# EtchSketch.net
KiCad netlist of a schematic drawn in EAGLE
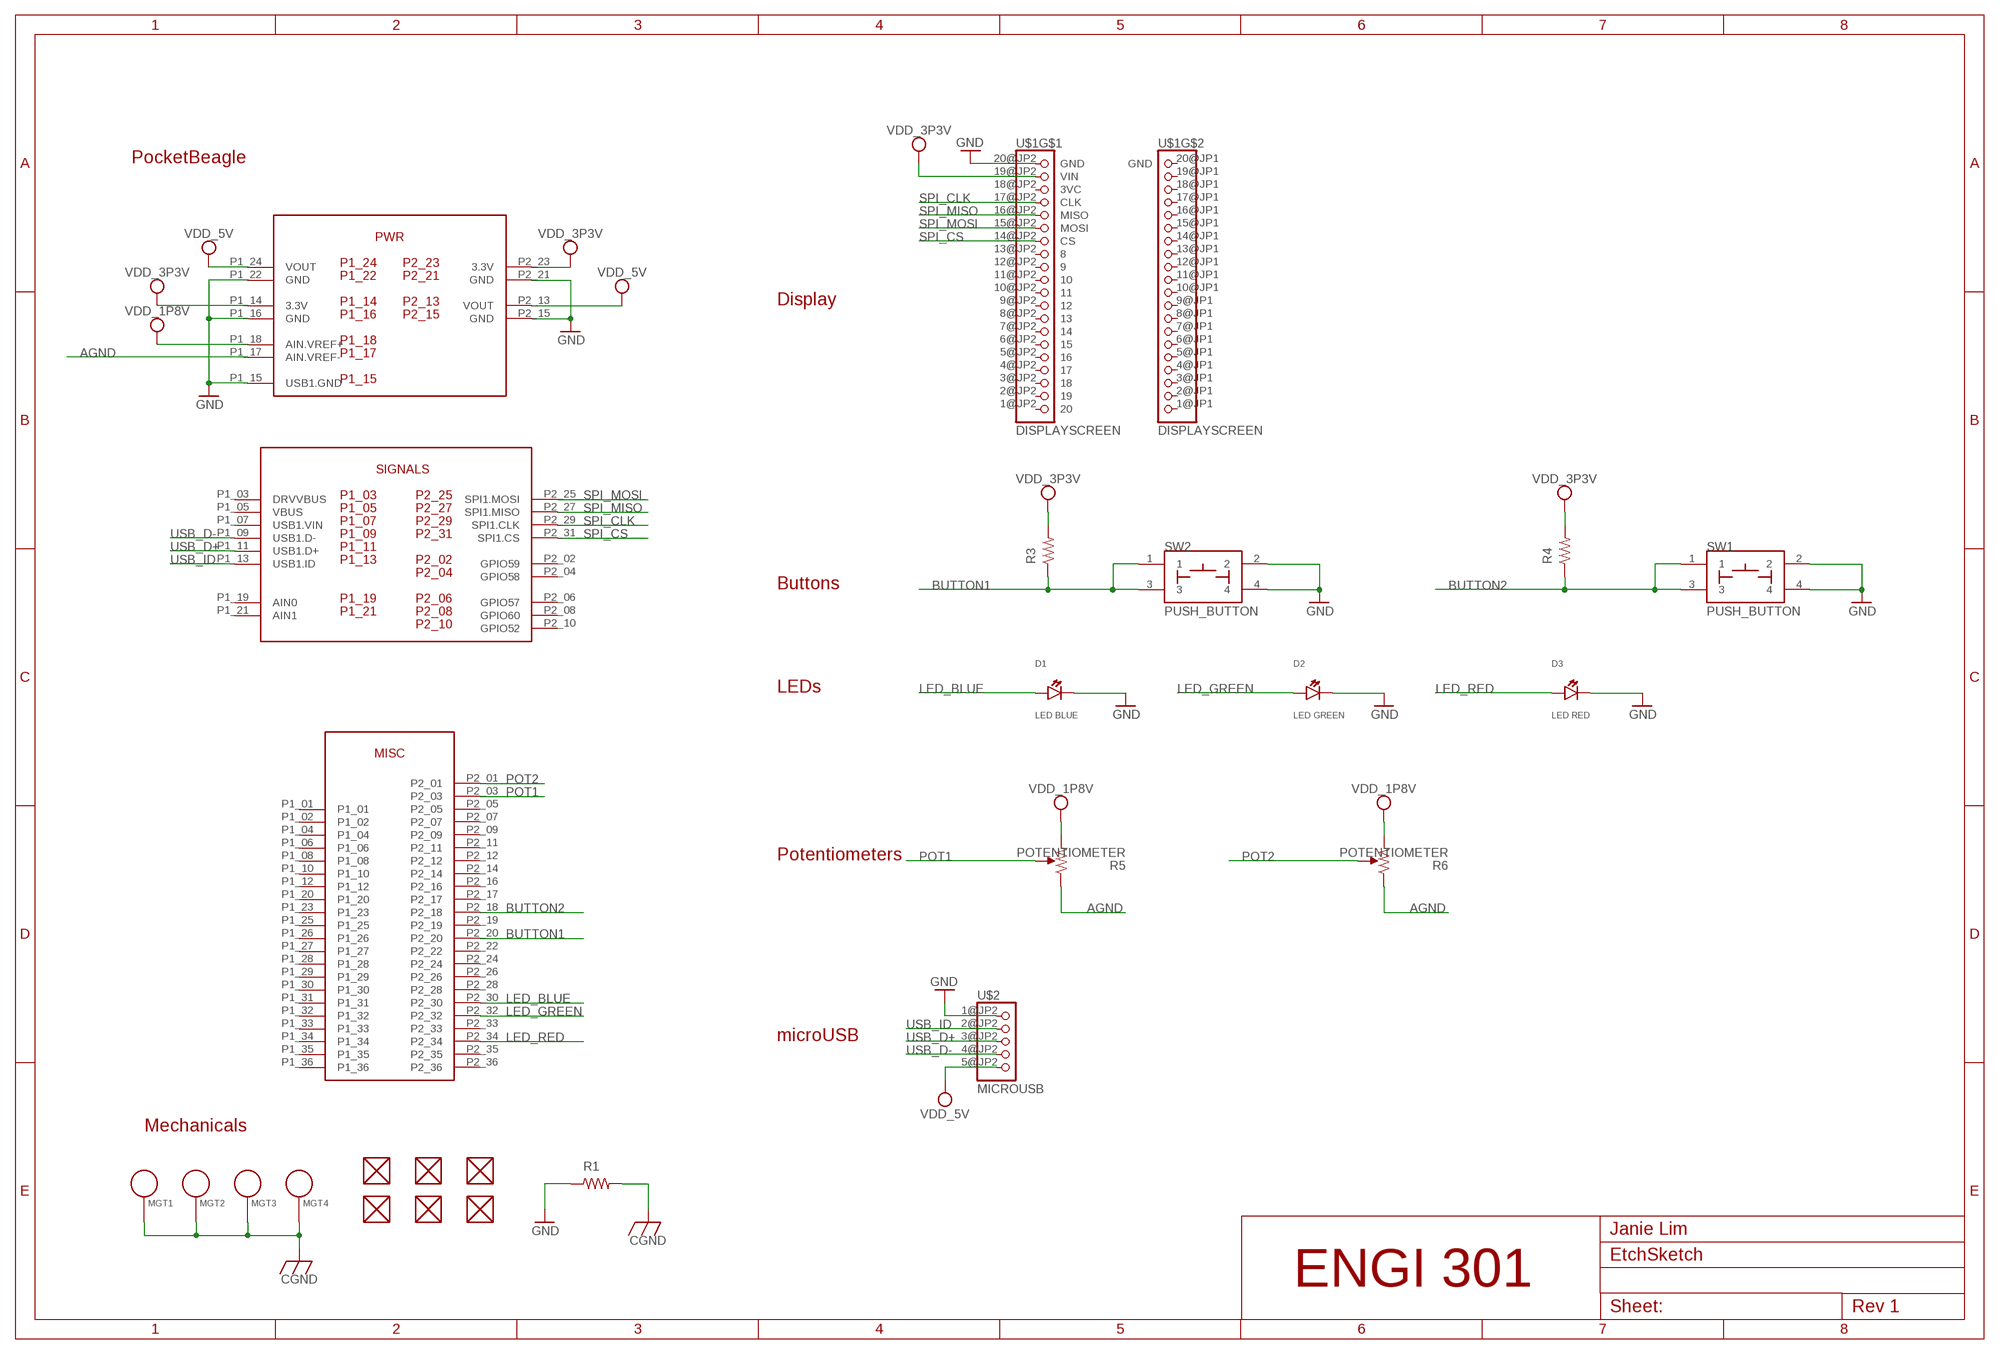
[diagram p0: schematic, sheet 1]

(export (version "E")
  (design (tool "Eeschema 10.0.6"))
  (components
    (comp (ref "D1")
      (value "LED BLUE")
      (footprint "eagle-import:EIA-STD")
      (libsource (lib "eagle-import") (part "LED"))
    )
    (comp (ref "D2")
      (value "LED GREEN")
      (footprint "eagle-import:EIA-STD")
      (libsource (lib "eagle-import") (part "LED"))
    )
    (comp (ref "D3")
      (value "LED RED")
      (footprint "eagle-import:EIA-STD")
      (libsource (lib "eagle-import") (part "LED"))
    )
    (comp (ref "FUD1")
      (value "FIDUCIAL")
      (footprint "eagle-import:FIDUCIAL_40MIL")
      (libsource (lib "eagle-import") (part "FIDUCIAL"))
    )
    (comp (ref "FUD2")
      (value "FIDUCIAL")
      (footprint "eagle-import:FIDUCIAL_40MIL")
      (libsource (lib "eagle-import") (part "FIDUCIAL"))
    )
    (comp (ref "FUD3")
      (value "FIDUCIAL")
      (footprint "eagle-import:FIDUCIAL_40MIL")
      (libsource (lib "eagle-import") (part "FIDUCIAL"))
    )
    (comp (ref "FUD4")
      (value "FIDUCIAL")
      (footprint "eagle-import:FIDUCIAL_40MIL")
      (libsource (lib "eagle-import") (part "FIDUCIAL"))
    )
    (comp (ref "FUD5")
      (value "FIDUCIAL")
      (footprint "eagle-import:FIDUCIAL_40MIL")
      (libsource (lib "eagle-import") (part "FIDUCIAL"))
    )
    (comp (ref "FUD6")
      (value "FIDUCIAL")
      (footprint "eagle-import:FIDUCIAL_40MIL")
      (libsource (lib "eagle-import") (part "FIDUCIAL"))
    )
    (comp (ref "MGT1")
      (value "MOUNTING_HOLE")
      (footprint "eagle-import:MOUNTING_HOLE")
      (libsource (lib "eagle-import") (part "MOUNTING_HOLE"))
    )
    (comp (ref "MGT2")
      (value "MOUNTING_HOLE")
      (footprint "eagle-import:MOUNTING_HOLE")
      (libsource (lib "eagle-import") (part "MOUNTING_HOLE"))
    )
    (comp (ref "MGT3")
      (value "MOUNTING_HOLE")
      (footprint "eagle-import:MOUNTING_HOLE")
      (libsource (lib "eagle-import") (part "MOUNTING_HOLE"))
    )
    (comp (ref "MGT4")
      (value "MOUNTING_HOLE")
      (footprint "eagle-import:MOUNTING_HOLE")
      (libsource (lib "eagle-import") (part "MOUNTING_HOLE"))
    )
    (comp (ref "R1")
      (value "R_R0603")
      (footprint "eagle-import:R0603")
      (libsource (lib "eagle-import") (part "R_R0603"))
    )
    (comp (ref "R3")
      (value "R_R0603")
      (footprint "eagle-import:R0603")
      (libsource (lib "eagle-import") (part "R_R0603"))
    )
    (comp (ref "R4")
      (value "R_R0603")
      (footprint "eagle-import:R0603")
      (libsource (lib "eagle-import") (part "R_R0603"))
    )
    (comp (ref "R5")
      (value "POTENTIOMETER")
      (footprint "eagle-import:POT-PO90S")
      (libsource (lib "eagle-import") (part "POTENTIOMETER"))
    )
    (comp (ref "R6")
      (value "POTENTIOMETER")
      (footprint "eagle-import:POT-PO90S")
      (libsource (lib "eagle-import") (part "POTENTIOMETER"))
    )
    (comp (ref "SW1")
      (value "PUSH_BUTTON")
      (footprint "eagle-import:BUTTON_12.5MM")
      (libsource (lib "eagle-import") (part "PUSH_BUTTON"))
    )
    (comp (ref "SW2")
      (value "PUSH_BUTTON")
      (footprint "eagle-import:BUTTON_12.5MM")
      (libsource (lib "eagle-import") (part "PUSH_BUTTON"))
    )
    (comp (ref "U$1")
      (value "DISPLAYSCREEN")
      (footprint "eagle-import:DISPLAYSCREEN")
      (libsource (lib "eagle-import") (part "DISPLAYSCREEN"))
    )
    (comp (ref "U$2")
      (value "MICROUSB")
      (footprint "eagle-import:MICROUSB")
      (libsource (lib "eagle-import") (part "MICROUSB"))
    )
    (comp (ref "U1")
      (value "POCKETBEAGLE_NEW")
      (footprint "eagle-import:POCKETBEAGLE")
      (libsource (lib "eagle-import") (part "POCKETBEAGLE_NEW"))
    )
  )
  (nets
    (net (code "1") (name "/AGND") (class "Default")
      (node (ref "R5") (pin "CCW") (pinfunction "CCW_CCW") (pintype "passive"))
      (node (ref "R6") (pin "CCW") (pinfunction "CCW_CCW") (pintype "passive"))
      (node (ref "U1") (pin "P1_17") (pinfunction "AIN.VREF-_P1_17") (pintype "bidirectional"))
    )
    (net (code "2") (name "/BUTTON1") (class "Default")
      (node (ref "R3") (pin "1") (pinfunction "1_1") (pintype "passive"))
      (node (ref "SW2") (pin "1") (pinfunction "1_1") (pintype "bidirectional"))
      (node (ref "SW2") (pin "3") (pinfunction "3_3") (pintype "bidirectional"))
      (node (ref "U1") (pin "P2_20") (pinfunction "P2_20_P2_20") (pintype "bidirectional"))
    )
    (net (code "3") (name "/BUTTON2") (class "Default")
      (node (ref "R4") (pin "1") (pinfunction "1_1") (pintype "passive"))
      (node (ref "SW1") (pin "1") (pinfunction "1_1") (pintype "bidirectional"))
      (node (ref "SW1") (pin "3") (pinfunction "3_3") (pintype "bidirectional"))
      (node (ref "U1") (pin "P2_18") (pinfunction "P2_18_P2_18") (pintype "bidirectional"))
    )
    (net (code "4") (name "/LED_BLUE") (class "Default")
      (node (ref "D1") (pin "ANODE") (pinfunction "ANODE_ANODE") (pintype "bidirectional"))
      (node (ref "U1") (pin "P2_30") (pinfunction "P2_30_P2_30") (pintype "bidirectional"))
    )
    (net (code "5") (name "/LED_GREEN") (class "Default")
      (node (ref "D2") (pin "ANODE") (pinfunction "ANODE_ANODE") (pintype "bidirectional"))
      (node (ref "U1") (pin "P2_32") (pinfunction "P2_32_P2_32") (pintype "bidirectional"))
    )
    (net (code "6") (name "/LED_RED") (class "Default")
      (node (ref "D3") (pin "ANODE") (pinfunction "ANODE_ANODE") (pintype "bidirectional"))
      (node (ref "U1") (pin "P2_34") (pinfunction "P2_34_P2_34") (pintype "bidirectional"))
    )
    (net (code "7") (name "/POT1") (class "Default")
      (node (ref "R5") (pin "S") (pinfunction "S_S") (pintype "bidirectional"))
      (node (ref "U1") (pin "P2_03") (pinfunction "P2_03_P2_03") (pintype "bidirectional"))
    )
    (net (code "8") (name "/POT2") (class "Default")
      (node (ref "R6") (pin "S") (pinfunction "S_S") (pintype "bidirectional"))
      (node (ref "U1") (pin "P2_01") (pinfunction "P2_01_P2_01") (pintype "bidirectional"))
    )
    (net (code "9") (name "/SPI_CLK") (class "Default")
      (node (ref "U$1") (pin "17@JP2") (pinfunction "CLK_17@JP2") (pintype "passive"))
      (node (ref "U1") (pin "P2_29") (pinfunction "SPI1.CLK_P2_29") (pintype "bidirectional"))
    )
    (net (code "10") (name "/SPI_CS") (class "Default")
      (node (ref "U$1") (pin "14@JP2") (pinfunction "CS_14@JP2") (pintype "passive"))
      (node (ref "U1") (pin "P2_31") (pinfunction "SPI1.CS_P2_31") (pintype "bidirectional"))
    )
    (net (code "11") (name "/SPI_MISO") (class "Default")
      (node (ref "U$1") (pin "16@JP2") (pinfunction "MISO_16@JP2") (pintype "passive"))
      (node (ref "U1") (pin "P2_27") (pinfunction "SPI1.MISO_P2_27") (pintype "bidirectional"))
    )
    (net (code "12") (name "/SPI_MOSI") (class "Default")
      (node (ref "U$1") (pin "15@JP2") (pinfunction "MOSI_15@JP2") (pintype "passive"))
      (node (ref "U1") (pin "P2_25") (pinfunction "SPI1.MOSI_P2_25") (pintype "bidirectional"))
    )
    (net (code "13") (name "/USB_D+") (class "Default")
      (node (ref "U$2") (pin "3@JP2") (pinfunction "D+_3@JP2") (pintype "passive"))
      (node (ref "U1") (pin "P1_11") (pinfunction "USB1.D+_P1_11") (pintype "bidirectional"))
    )
    (net (code "14") (name "/USB_D-") (class "Default")
      (node (ref "U$2") (pin "4@JP2") (pinfunction "D-_4@JP2") (pintype "passive"))
      (node (ref "U1") (pin "P1_09") (pinfunction "USB1.D-_P1_09") (pintype "bidirectional"))
    )
    (net (code "15") (name "/USB_ID") (class "Default")
      (node (ref "U$2") (pin "2@JP2") (pinfunction "ID_2@JP2") (pintype "passive"))
      (node (ref "U1") (pin "P1_13") (pinfunction "USB1.ID_P1_13") (pintype "bidirectional"))
    )
    (net (code "16") (name "CGND") (class "Default")
      (node (ref "MGT1") (pin "P$1") (pinfunction "P$1_P$1") (pintype "bidirectional"))
      (node (ref "MGT2") (pin "P$1") (pinfunction "P$1_P$1") (pintype "bidirectional"))
      (node (ref "MGT3") (pin "P$1") (pinfunction "P$1_P$1") (pintype "bidirectional"))
      (node (ref "MGT4") (pin "P$1") (pinfunction "P$1_P$1") (pintype "bidirectional"))
      (node (ref "R1") (pin "2") (pinfunction "2_2") (pintype "passive"))
    )
    (net (code "17") (name "GND") (class "Default")
      (node (ref "D1") (pin "CATHODE") (pinfunction "CATHODE_CATHODE") (pintype "bidirectional"))
      (node (ref "D2") (pin "CATHODE") (pinfunction "CATHODE_CATHODE") (pintype "bidirectional"))
      (node (ref "D3") (pin "CATHODE") (pinfunction "CATHODE_CATHODE") (pintype "bidirectional"))
      (node (ref "R1") (pin "1") (pinfunction "1_1") (pintype "passive"))
      (node (ref "SW1") (pin "2") (pinfunction "2_2") (pintype "bidirectional"))
      (node (ref "SW1") (pin "4") (pinfunction "4_4") (pintype "bidirectional"))
      (node (ref "SW2") (pin "2") (pinfunction "2_2") (pintype "bidirectional"))
      (node (ref "SW2") (pin "4") (pinfunction "4_4") (pintype "bidirectional"))
      (node (ref "U$1") (pin "20@JP2") (pinfunction "GND_20@JP2") (pintype "passive"))
      (node (ref "U$2") (pin "1@JP2") (pinfunction "GND_1@JP2") (pintype "passive"))
      (node (ref "U1") (pin "P1_15") (pinfunction "USB1.GND_P1_15") (pintype "bidirectional"))
      (node (ref "U1") (pin "P1_16") (pinfunction "GND_P1_16") (pintype "power_in"))
      (node (ref "U1") (pin "P1_22") (pinfunction "GND_P1_22") (pintype "power_in"))
      (node (ref "U1") (pin "P2_15") (pinfunction "GND_P2_15") (pintype "power_in"))
      (node (ref "U1") (pin "P2_21") (pinfunction "GND_P2_21") (pintype "power_in"))
    )
    (net (code "18") (name "VDD_1P8V") (class "Default")
      (node (ref "R5") (pin "CW") (pinfunction "CW_CW") (pintype "passive"))
      (node (ref "R6") (pin "CW") (pinfunction "CW_CW") (pintype "passive"))
      (node (ref "U1") (pin "P1_18") (pinfunction "AIN.VREF+_P1_18") (pintype "bidirectional"))
    )
    (net (code "19") (name "VDD_3P3V") (class "Default")
      (node (ref "R3") (pin "2") (pinfunction "2_2") (pintype "passive"))
      (node (ref "R4") (pin "2") (pinfunction "2_2") (pintype "passive"))
      (node (ref "U$1") (pin "19@JP2") (pinfunction "VIN_19@JP2") (pintype "passive"))
      (node (ref "U1") (pin "P1_14") (pinfunction "3.3V_P1_14") (pintype "power_in"))
      (node (ref "U1") (pin "P2_23") (pinfunction "3.3V_P2_23") (pintype "power_in"))
    )
    (net (code "20") (name "VDD_5V") (class "Default")
      (node (ref "U$2") (pin "5@JP2") (pinfunction "5V_5@JP2") (pintype "passive"))
      (node (ref "U1") (pin "P1_24") (pinfunction "VOUT_P1_24") (pintype "power_in"))
      (node (ref "U1") (pin "P2_13") (pinfunction "VOUT_P2_13") (pintype "power_in"))
    )
    (net (code "21") (name "unconnected-(FUD1-PadP$1)") (class "Default")
      (node (ref "FUD1") (pin "P$1") (pinfunction "P$1_P$1") (pintype "no_connect"))
    )
    (net (code "22") (name "unconnected-(FUD2-PadP$1)") (class "Default")
      (node (ref "FUD2") (pin "P$1") (pinfunction "P$1_P$1") (pintype "no_connect"))
    )
    (net (code "23") (name "unconnected-(FUD3-PadP$1)") (class "Default")
      (node (ref "FUD3") (pin "P$1") (pinfunction "P$1_P$1") (pintype "no_connect"))
    )
    (net (code "24") (name "unconnected-(FUD4-PadP$1)") (class "Default")
      (node (ref "FUD4") (pin "P$1") (pinfunction "P$1_P$1") (pintype "no_connect"))
    )
    (net (code "25") (name "unconnected-(FUD5-PadP$1)") (class "Default")
      (node (ref "FUD5") (pin "P$1") (pinfunction "P$1_P$1") (pintype "no_connect"))
    )
    (net (code "26") (name "unconnected-(FUD6-PadP$1)") (class "Default")
      (node (ref "FUD6") (pin "P$1") (pinfunction "P$1_P$1") (pintype "no_connect"))
    )
    (net (code "27") (name "unconnected-(U$1A-3VC-Pad18@JP2)") (class "Default")
      (node (ref "U$1") (pin "18@JP2") (pinfunction "3VC_18@JP2") (pintype "passive"))
    )
    (net (code "28") (name "unconnected-(U$1A-8-Pad13@JP2)") (class "Default")
      (node (ref "U$1") (pin "13@JP2") (pinfunction "8_13@JP2") (pintype "passive"))
    )
    (net (code "29") (name "unconnected-(U$1A-9-Pad12@JP2)") (class "Default")
      (node (ref "U$1") (pin "12@JP2") (pinfunction "9_12@JP2") (pintype "passive"))
    )
    (net (code "30") (name "unconnected-(U$1A-10-Pad11@JP2)") (class "Default")
      (node (ref "U$1") (pin "11@JP2") (pinfunction "10_11@JP2") (pintype "passive"))
    )
    (net (code "31") (name "unconnected-(U$1A-11-Pad10@JP2)") (class "Default")
      (node (ref "U$1") (pin "10@JP2") (pinfunction "11_10@JP2") (pintype "passive"))
    )
    (net (code "32") (name "unconnected-(U$1A-12-Pad9@JP2)") (class "Default")
      (node (ref "U$1") (pin "9@JP2") (pinfunction "12_9@JP2") (pintype "passive"))
    )
    (net (code "33") (name "unconnected-(U$1A-13-Pad8@JP2)") (class "Default")
      (node (ref "U$1") (pin "8@JP2") (pinfunction "13_8@JP2") (pintype "passive"))
    )
    (net (code "34") (name "unconnected-(U$1A-14-Pad7@JP2)") (class "Default")
      (node (ref "U$1") (pin "7@JP2") (pinfunction "14_7@JP2") (pintype "passive"))
    )
    (net (code "35") (name "unconnected-(U$1A-15-Pad6@JP2)") (class "Default")
      (node (ref "U$1") (pin "6@JP2") (pinfunction "15_6@JP2") (pintype "passive"))
    )
    (net (code "36") (name "unconnected-(U$1A-16-Pad5@JP2)") (class "Default")
      (node (ref "U$1") (pin "5@JP2") (pinfunction "16_5@JP2") (pintype "passive"))
    )
    (net (code "37") (name "unconnected-(U$1A-17-Pad4@JP2)") (class "Default")
      (node (ref "U$1") (pin "4@JP2") (pinfunction "17_4@JP2") (pintype "passive"))
    )
    (net (code "38") (name "unconnected-(U$1A-18-Pad3@JP2)") (class "Default")
      (node (ref "U$1") (pin "3@JP2") (pinfunction "18_3@JP2") (pintype "passive"))
    )
    (net (code "39") (name "unconnected-(U$1A-19-Pad2@JP2)") (class "Default")
      (node (ref "U$1") (pin "2@JP2") (pinfunction "19_2@JP2") (pintype "passive"))
    )
    (net (code "40") (name "unconnected-(U$1A-20-Pad1@JP2)") (class "Default")
      (node (ref "U$1") (pin "1@JP2") (pinfunction "20_1@JP2") (pintype "passive"))
    )
    (net (code "41") (name "unconnected-(U$1B-2-Pad19@JP1)") (class "Default")
      (node (ref "U$1") (pin "19@JP1") (pinfunction "2_19@JP1") (pintype "passive"))
    )
    (net (code "42") (name "unconnected-(U$1B-3-Pad18@JP1)") (class "Default")
      (node (ref "U$1") (pin "18@JP1") (pinfunction "3_18@JP1") (pintype "passive"))
    )
    (net (code "43") (name "unconnected-(U$1B-4-Pad17@JP1)") (class "Default")
      (node (ref "U$1") (pin "17@JP1") (pinfunction "4_17@JP1") (pintype "passive"))
    )
    (net (code "44") (name "unconnected-(U$1B-5-Pad16@JP1)") (class "Default")
      (node (ref "U$1") (pin "16@JP1") (pinfunction "5_16@JP1") (pintype "passive"))
    )
    (net (code "45") (name "unconnected-(U$1B-6-Pad15@JP1)") (class "Default")
      (node (ref "U$1") (pin "15@JP1") (pinfunction "6_15@JP1") (pintype "passive"))
    )
    (net (code "46") (name "unconnected-(U$1B-7-Pad14@JP1)") (class "Default")
      (node (ref "U$1") (pin "14@JP1") (pinfunction "7_14@JP1") (pintype "passive"))
    )
    (net (code "47") (name "unconnected-(U$1B-8-Pad13@JP1)") (class "Default")
      (node (ref "U$1") (pin "13@JP1") (pinfunction "8_13@JP1") (pintype "passive"))
    )
    (net (code "48") (name "unconnected-(U$1B-9-Pad12@JP1)") (class "Default")
      (node (ref "U$1") (pin "12@JP1") (pinfunction "9_12@JP1") (pintype "passive"))
    )
    (net (code "49") (name "unconnected-(U$1B-10-Pad11@JP1)") (class "Default")
      (node (ref "U$1") (pin "11@JP1") (pinfunction "10_11@JP1") (pintype "passive"))
    )
    (net (code "50") (name "unconnected-(U$1B-11-Pad10@JP1)") (class "Default")
      (node (ref "U$1") (pin "10@JP1") (pinfunction "11_10@JP1") (pintype "passive"))
    )
    (net (code "51") (name "unconnected-(U$1B-12-Pad9@JP1)") (class "Default")
      (node (ref "U$1") (pin "9@JP1") (pinfunction "12_9@JP1") (pintype "passive"))
    )
    (net (code "52") (name "unconnected-(U$1B-13-Pad8@JP1)") (class "Default")
      (node (ref "U$1") (pin "8@JP1") (pinfunction "13_8@JP1") (pintype "passive"))
    )
    (net (code "53") (name "unconnected-(U$1B-14-Pad7@JP1)") (class "Default")
      (node (ref "U$1") (pin "7@JP1") (pinfunction "14_7@JP1") (pintype "passive"))
    )
    (net (code "54") (name "unconnected-(U$1B-15-Pad6@JP1)") (class "Default")
      (node (ref "U$1") (pin "6@JP1") (pinfunction "15_6@JP1") (pintype "passive"))
    )
    (net (code "55") (name "unconnected-(U$1B-16-Pad5@JP1)") (class "Default")
      (node (ref "U$1") (pin "5@JP1") (pinfunction "16_5@JP1") (pintype "passive"))
    )
    (net (code "56") (name "unconnected-(U$1B-17-Pad4@JP1)") (class "Default")
      (node (ref "U$1") (pin "4@JP1") (pinfunction "17_4@JP1") (pintype "passive"))
    )
    (net (code "57") (name "unconnected-(U$1B-18-Pad3@JP1)") (class "Default")
      (node (ref "U$1") (pin "3@JP1") (pinfunction "18_3@JP1") (pintype "passive"))
    )
    (net (code "58") (name "unconnected-(U$1B-19-Pad2@JP1)") (class "Default")
      (node (ref "U$1") (pin "2@JP1") (pinfunction "19_2@JP1") (pintype "passive"))
    )
    (net (code "59") (name "unconnected-(U$1B-20-Pad1@JP1)") (class "Default")
      (node (ref "U$1") (pin "1@JP1") (pinfunction "20_1@JP1") (pintype "passive"))
    )
    (net (code "60") (name "unconnected-(U$1B-GND-Pad20@JP1)") (class "Default")
      (node (ref "U$1") (pin "20@JP1") (pinfunction "GND_20@JP1") (pintype "passive"))
    )
    (net (code "61") (name "unconnected-(U1-PadP1_01)") (class "Default")
      (node (ref "U1") (pin "P1_01") (pinfunction "P1_01_P1_01") (pintype "bidirectional"))
    )
    (net (code "62") (name "unconnected-(U1-PadP1_02)") (class "Default")
      (node (ref "U1") (pin "P1_02") (pinfunction "P1_02_P1_02") (pintype "bidirectional"))
    )
    (net (code "63") (name "unconnected-(U1-PadP1_04)") (class "Default")
      (node (ref "U1") (pin "P1_04") (pinfunction "P1_04_P1_04") (pintype "bidirectional"))
    )
    (net (code "64") (name "unconnected-(U1-PadP1_06)") (class "Default")
      (node (ref "U1") (pin "P1_06") (pinfunction "P1_06_P1_06") (pintype "bidirectional"))
    )
    (net (code "65") (name "unconnected-(U1-PadP1_08)") (class "Default")
      (node (ref "U1") (pin "P1_08") (pinfunction "P1_08_P1_08") (pintype "bidirectional"))
    )
    (net (code "66") (name "unconnected-(U1-PadP1_10)") (class "Default")
      (node (ref "U1") (pin "P1_10") (pinfunction "P1_10_P1_10") (pintype "bidirectional"))
    )
    (net (code "67") (name "unconnected-(U1-PadP1_12)") (class "Default")
      (node (ref "U1") (pin "P1_12") (pinfunction "P1_12_P1_12") (pintype "bidirectional"))
    )
    (net (code "68") (name "unconnected-(U1-PadP1_20)") (class "Default")
      (node (ref "U1") (pin "P1_20") (pinfunction "P1_20_P1_20") (pintype "bidirectional"))
    )
    (net (code "69") (name "unconnected-(U1-PadP1_23)") (class "Default")
      (node (ref "U1") (pin "P1_23") (pinfunction "P1_23_P1_23") (pintype "bidirectional"))
    )
    (net (code "70") (name "unconnected-(U1-PadP1_25)") (class "Default")
      (node (ref "U1") (pin "P1_25") (pinfunction "P1_25_P1_25") (pintype "bidirectional"))
    )
    (net (code "71") (name "unconnected-(U1-PadP1_26)") (class "Default")
      (node (ref "U1") (pin "P1_26") (pinfunction "P1_26_P1_26") (pintype "bidirectional"))
    )
    (net (code "72") (name "unconnected-(U1-PadP1_27)") (class "Default")
      (node (ref "U1") (pin "P1_27") (pinfunction "P1_27_P1_27") (pintype "bidirectional"))
    )
    (net (code "73") (name "unconnected-(U1-PadP1_28)") (class "Default")
      (node (ref "U1") (pin "P1_28") (pinfunction "P1_28_P1_28") (pintype "bidirectional"))
    )
    (net (code "74") (name "unconnected-(U1-PadP1_29)") (class "Default")
      (node (ref "U1") (pin "P1_29") (pinfunction "P1_29_P1_29") (pintype "bidirectional"))
    )
    (net (code "75") (name "unconnected-(U1-PadP1_30)") (class "Default")
      (node (ref "U1") (pin "P1_30") (pinfunction "P1_30_P1_30") (pintype "bidirectional"))
    )
    (net (code "76") (name "unconnected-(U1-PadP1_31)") (class "Default")
      (node (ref "U1") (pin "P1_31") (pinfunction "P1_31_P1_31") (pintype "bidirectional"))
    )
    (net (code "77") (name "unconnected-(U1-PadP1_32)") (class "Default")
      (node (ref "U1") (pin "P1_32") (pinfunction "P1_32_P1_32") (pintype "bidirectional"))
    )
    (net (code "78") (name "unconnected-(U1-PadP1_33)") (class "Default")
      (node (ref "U1") (pin "P1_33") (pinfunction "P1_33_P1_33") (pintype "bidirectional"))
    )
    (net (code "79") (name "unconnected-(U1-PadP1_34)") (class "Default")
      (node (ref "U1") (pin "P1_34") (pinfunction "P1_34_P1_34") (pintype "bidirectional"))
    )
    (net (code "80") (name "unconnected-(U1-PadP1_35)") (class "Default")
      (node (ref "U1") (pin "P1_35") (pinfunction "P1_35_P1_35") (pintype "bidirectional"))
    )
    (net (code "81") (name "unconnected-(U1-PadP1_36)") (class "Default")
      (node (ref "U1") (pin "P1_36") (pinfunction "P1_36_P1_36") (pintype "bidirectional"))
    )
    (net (code "82") (name "unconnected-(U1-PadP2_05)") (class "Default")
      (node (ref "U1") (pin "P2_05") (pinfunction "P2_05_P2_05") (pintype "bidirectional"))
    )
    (net (code "83") (name "unconnected-(U1-PadP2_07)") (class "Default")
      (node (ref "U1") (pin "P2_07") (pinfunction "P2_07_P2_07") (pintype "bidirectional"))
    )
    (net (code "84") (name "unconnected-(U1-PadP2_09)") (class "Default")
      (node (ref "U1") (pin "P2_09") (pinfunction "P2_09_P2_09") (pintype "bidirectional"))
    )
    (net (code "85") (name "unconnected-(U1-PadP2_11)") (class "Default")
      (node (ref "U1") (pin "P2_11") (pinfunction "P2_11_P2_11") (pintype "bidirectional"))
    )
    (net (code "86") (name "unconnected-(U1-PadP2_12)") (class "Default")
      (node (ref "U1") (pin "P2_12") (pinfunction "P2_12_P2_12") (pintype "bidirectional"))
    )
    (net (code "87") (name "unconnected-(U1-PadP2_14)") (class "Default")
      (node (ref "U1") (pin "P2_14") (pinfunction "P2_14_P2_14") (pintype "bidirectional"))
    )
    (net (code "88") (name "unconnected-(U1-PadP2_16)") (class "Default")
      (node (ref "U1") (pin "P2_16") (pinfunction "P2_16_P2_16") (pintype "bidirectional"))
    )
    (net (code "89") (name "unconnected-(U1-PadP2_17)") (class "Default")
      (node (ref "U1") (pin "P2_17") (pinfunction "P2_17_P2_17") (pintype "bidirectional"))
    )
    (net (code "90") (name "unconnected-(U1-PadP2_19)") (class "Default")
      (node (ref "U1") (pin "P2_19") (pinfunction "P2_19_P2_19") (pintype "bidirectional"))
    )
    (net (code "91") (name "unconnected-(U1-PadP2_22)") (class "Default")
      (node (ref "U1") (pin "P2_22") (pinfunction "P2_22_P2_22") (pintype "bidirectional"))
    )
    (net (code "92") (name "unconnected-(U1-PadP2_24)") (class "Default")
      (node (ref "U1") (pin "P2_24") (pinfunction "P2_24_P2_24") (pintype "bidirectional"))
    )
    (net (code "93") (name "unconnected-(U1-PadP2_26)") (class "Default")
      (node (ref "U1") (pin "P2_26") (pinfunction "P2_26_P2_26") (pintype "bidirectional"))
    )
    (net (code "94") (name "unconnected-(U1-PadP2_28)") (class "Default")
      (node (ref "U1") (pin "P2_28") (pinfunction "P2_28_P2_28") (pintype "bidirectional"))
    )
    (net (code "95") (name "unconnected-(U1-PadP2_33)") (class "Default")
      (node (ref "U1") (pin "P2_33") (pinfunction "P2_33_P2_33") (pintype "bidirectional"))
    )
    (net (code "96") (name "unconnected-(U1-PadP2_35)") (class "Default")
      (node (ref "U1") (pin "P2_35") (pinfunction "P2_35_P2_35") (pintype "bidirectional"))
    )
    (net (code "97") (name "unconnected-(U1-PadP2_36)") (class "Default")
      (node (ref "U1") (pin "P2_36") (pinfunction "P2_36_P2_36") (pintype "bidirectional"))
    )
    (net (code "98") (name "unconnected-(U1B-AIN0-PadP1_19)") (class "Default")
      (node (ref "U1") (pin "P1_19") (pinfunction "AIN0_P1_19") (pintype "bidirectional"))
    )
    (net (code "99") (name "unconnected-(U1B-AIN1-PadP1_21)") (class "Default")
      (node (ref "U1") (pin "P1_21") (pinfunction "AIN1_P1_21") (pintype "bidirectional"))
    )
    (net (code "100") (name "unconnected-(U1B-DRVVBUS-PadP1_03)") (class "Default")
      (node (ref "U1") (pin "P1_03") (pinfunction "DRVVBUS_P1_03") (pintype "bidirectional"))
    )
    (net (code "101") (name "unconnected-(U1B-GPIO52-PadP2_10)") (class "Default")
      (node (ref "U1") (pin "P2_10") (pinfunction "GPIO52_P2_10") (pintype "bidirectional"))
    )
    (net (code "102") (name "unconnected-(U1B-GPIO57-PadP2_06)") (class "Default")
      (node (ref "U1") (pin "P2_06") (pinfunction "GPIO57_P2_06") (pintype "bidirectional"))
    )
    (net (code "103") (name "unconnected-(U1B-GPIO58-PadP2_04)") (class "Default")
      (node (ref "U1") (pin "P2_04") (pinfunction "GPIO58_P2_04") (pintype "bidirectional"))
    )
    (net (code "104") (name "unconnected-(U1B-GPIO59-PadP2_02)") (class "Default")
      (node (ref "U1") (pin "P2_02") (pinfunction "GPIO59_P2_02") (pintype "bidirectional"))
    )
    (net (code "105") (name "unconnected-(U1B-GPIO60-PadP2_08)") (class "Default")
      (node (ref "U1") (pin "P2_08") (pinfunction "GPIO60_P2_08") (pintype "bidirectional"))
    )
    (net (code "106") (name "unconnected-(U1B-USB1.VIN-PadP1_07)") (class "Default")
      (node (ref "U1") (pin "P1_07") (pinfunction "USB1.VIN_P1_07") (pintype "bidirectional"))
    )
    (net (code "107") (name "unconnected-(U1B-VBUS-PadP1_05)") (class "Default")
      (node (ref "U1") (pin "P1_05") (pinfunction "VBUS_P1_05") (pintype "bidirectional"))
    )
  )
)
